# PMU.net
KiCad netlist of a schematic drawn in Altium Designer
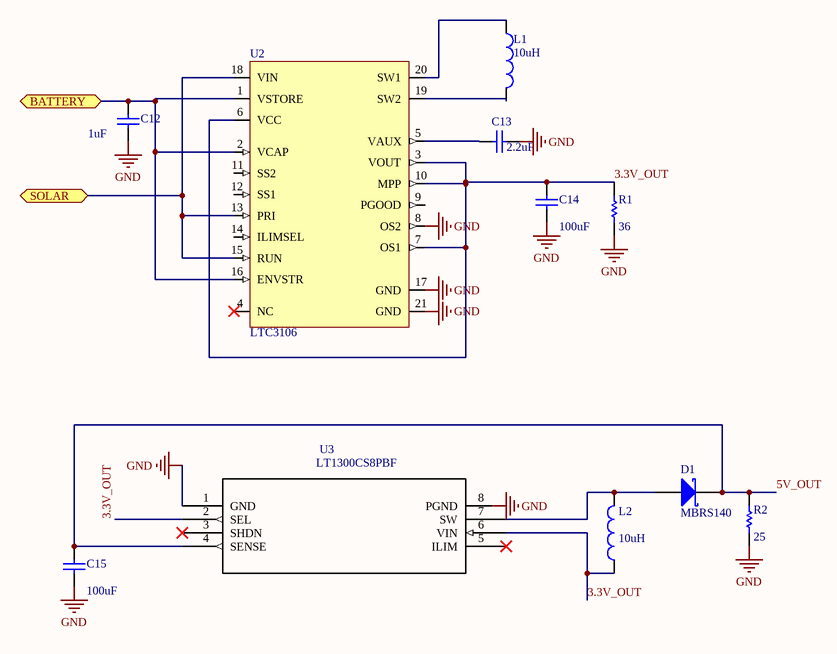
[diagram p0: PMU.SchDoc]

(export (version "E")
  (design (tool "Eeschema 10.0.6"))
  (components
    (comp (ref "C12")
      (value "1uF")
      (footprint "RAD-0.3")
      (description "Capacitor")
      (fields (field (name "Comment") "Cap") (field (name "PUBLISHER") "Altium Limited"))
      (libsource (lib "Miscellaneous Devices") (part "Cap"))
    )
    (comp (ref "C13")
      (value "2.2uF")
      (footprint "RAD-0.3")
      (description "Capacitor")
      (fields (field (name "Comment") "Cap") (field (name "PUBLISHER") "Altium Limited"))
      (libsource (lib "Miscellaneous Devices") (part "Cap"))
    )
    (comp (ref "C14")
      (value "100uF")
      (footprint "RAD-0.3")
      (description "Capacitor")
      (fields (field (name "Comment") "Cap") (field (name "PUBLISHER") "Altium Limited"))
      (libsource (lib "Miscellaneous Devices") (part "Cap"))
    )
    (comp (ref "C15")
      (value "100uF")
      (footprint "RAD-0.3")
      (description "Capacitor")
      (fields (field (name "Comment") "Cap") (field (name "PUBLISHER") "Altium Limited"))
      (libsource (lib "Miscellaneous Devices") (part "Cap"))
    )
    (comp (ref "D1")
      (value "MBRS140")
      (footprint "TO-220AC")
      (description "Schottky Rectifier")
      (fields (field (name "PUBLISHER") "Altium Limited"))
      (libsource (lib "Miscellaneous Devices") (part "Diode 10TQ040"))
    )
    (comp (ref "L1")
      (value "10uH")
      (footprint "0402-A")
      (description "Inductor")
      (fields (field (name "PUBLISHER") "Altium Limited"))
      (libsource (lib "Miscellaneous Devices") (part "Inductor"))
    )
    (comp (ref "L2")
      (value "10uH")
      (footprint "0402-A")
      (description "Inductor")
      (fields (field (name "PUBLISHER") "Altium Limited"))
      (libsource (lib "Miscellaneous Devices") (part "Inductor"))
    )
    (comp (ref "R1")
      (value "36")
      (footprint "AXIAL-0.3")
      (description "Resistor")
      (fields (field (name "Comment") "Res1") (field (name "PUBLISHER") "Altium Limited"))
      (libsource (lib "Miscellaneous Devices") (part "Res1"))
    )
    (comp (ref "R2")
      (value "25")
      (footprint "AXIAL-0.3")
      (description "Resistor")
      (fields (field (name "Comment") "Res1") (field (name "PUBLISHER") "Altium Limited"))
      (libsource (lib "Miscellaneous Devices") (part "Res1"))
    )
    (comp (ref "U2")
      (value "LTC3106")
      (footprint "LTC3106")
      (libsource (lib "LowPower_3ER_Parts") (part "LTC3106"))
    )
    (comp (ref "U3")
      (value "LT1300CS8PBF")
      (footprint "SOIC-8_S")
      (fields (field (name "MP") "LT1300CS8#PBF") (field (name "MF") "Linear Technology"))
      (libsource (lib "LowPower_3ER_Parts") (part "LT1300CS8PBF"))
    )
  )
  (nets
    (net (code "1") (name "/3.3V_OUT") (class "Default")
      (node (ref "C14") (pin "2") (pinfunction "2_2") (pintype "passive"))
      (node (ref "L2") (pin "1") (pinfunction "1_1") (pintype "passive"))
      (node (ref "R1") (pin "2") (pinfunction "2_2") (pintype "passive"))
      (node (ref "U2") (pin "10") (pinfunction "MPP_10") (pintype "output"))
      (node (ref "U2") (pin "3") (pinfunction "VOUT_3") (pintype "output"))
      (node (ref "U2") (pin "6") (pinfunction "VCC_6") (pintype "power_in"))
      (node (ref "U2") (pin "7") (pinfunction "OS1_7") (pintype "output"))
      (node (ref "U3") (pin "2") (pinfunction "SEL_2") (pintype "output"))
      (node (ref "U3") (pin "6") (pinfunction "VIN_6") (pintype "input"))
    )
    (net (code "2") (name "/5V_OUT") (class "Default")
      (node (ref "C15") (pin "2") (pinfunction "2_2") (pintype "passive"))
      (node (ref "D1") (pin "1") (pinfunction "K_1") (pintype "passive"))
      (node (ref "R2") (pin "2") (pinfunction "2_2") (pintype "passive"))
      (node (ref "U3") (pin "4") (pinfunction "SENSE_4") (pintype "output"))
    )
    (net (code "3") (name "/BATTERY") (class "Default")
      (node (ref "C12") (pin "2") (pinfunction "2_2") (pintype "passive"))
      (node (ref "U2") (pin "1") (pinfunction "VSTORE_1") (pintype "power_in"))
      (node (ref "U2") (pin "16") (pinfunction "ENVSTR_16") (pintype "input"))
      (node (ref "U2") (pin "2") (pinfunction "VCAP_2") (pintype "input"))
    )
    (net (code "4") (name "/SOLAR") (class "Default")
      (node (ref "U2") (pin "13") (pinfunction "PRI_13") (pintype "input"))
      (node (ref "U2") (pin "15") (pinfunction "RUN_15") (pintype "input"))
      (node (ref "U2") (pin "18") (pinfunction "VIN_18") (pintype "power_in"))
    )
    (net (code "5") (name "GND") (class "Default")
      (node (ref "C12") (pin "1") (pinfunction "1_1") (pintype "passive"))
      (node (ref "C13") (pin "2") (pinfunction "2_2") (pintype "passive"))
      (node (ref "C14") (pin "1") (pinfunction "1_1") (pintype "passive"))
      (node (ref "C15") (pin "1") (pinfunction "1_1") (pintype "passive"))
      (node (ref "R1") (pin "1") (pinfunction "1_1") (pintype "passive"))
      (node (ref "R2") (pin "1") (pinfunction "1_1") (pintype "passive"))
      (node (ref "U2") (pin "17") (pinfunction "GND_17") (pintype "power_in"))
      (node (ref "U2") (pin "21") (pinfunction "GND_21") (pintype "power_in"))
      (node (ref "U2") (pin "8") (pinfunction "OS2_8") (pintype "output"))
      (node (ref "U3") (pin "1") (pinfunction "GND_1") (pintype "power_in"))
    )
    (net (code "6") (name "Net-(D1-A)") (class "Default")
      (node (ref "D1") (pin "3") (pinfunction "A_3") (pintype "passive"))
      (node (ref "L2") (pin "2") (pinfunction "2_2") (pintype "passive"))
      (node (ref "U3") (pin "7") (pinfunction "SW_7") (pintype "passive"))
    )
    (net (code "7") (name "Net-(U2-SW1)") (class "Default")
      (node (ref "L1") (pin "1") (pinfunction "1_1") (pintype "passive"))
      (node (ref "U2") (pin "20") (pinfunction "SW1_20") (pintype "passive"))
    )
    (net (code "8") (name "Net-(U2-SW2)") (class "Default")
      (node (ref "L1") (pin "2") (pinfunction "2_2") (pintype "passive"))
      (node (ref "U2") (pin "19") (pinfunction "SW2_19") (pintype "passive"))
    )
    (net (code "9") (name "Net-(U2-VAUX)") (class "Default")
      (node (ref "C13") (pin "1") (pinfunction "1_1") (pintype "passive"))
      (node (ref "U2") (pin "5") (pinfunction "VAUX_5") (pintype "output"))
    )
    (net (code "10") (name "unconnected-(U2-ILIMSEL-Pad14)") (class "Default")
      (node (ref "U2") (pin "14") (pinfunction "ILIMSEL_14") (pintype "input"))
    )
    (net (code "11") (name "unconnected-(U2-NC-Pad4)") (class "Default")
      (node (ref "U2") (pin "4") (pinfunction "NC_4") (pintype "passive+no_connect"))
    )
    (net (code "12") (name "unconnected-(U2-PGOOD-Pad9)") (class "Default")
      (node (ref "U2") (pin "9") (pinfunction "PGOOD_9") (pintype "output"))
    )
    (net (code "13") (name "unconnected-(U2-SS1-Pad12)") (class "Default")
      (node (ref "U2") (pin "12") (pinfunction "SS1_12") (pintype "input"))
    )
    (net (code "14") (name "unconnected-(U2-SS2-Pad11)") (class "Default")
      (node (ref "U2") (pin "11") (pinfunction "SS2_11") (pintype "input"))
    )
    (net (code "15") (name "unconnected-(U3-ILIM-Pad5)") (class "Default")
      (node (ref "U3") (pin "5") (pinfunction "ILIM_5") (pintype "passive+no_connect"))
    )
    (net (code "16") (name "unconnected-(U3-PGND-Pad8)") (class "Default")
      (node (ref "U3") (pin "8") (pinfunction "PGND_8") (pintype "power_in"))
    )
    (net (code "17") (name "unconnected-(U3-SHDN-Pad3)") (class "Default")
      (node (ref "U3") (pin "3") (pinfunction "SHDN_3") (pintype "passive+no_connect"))
    )
  )
)
